# lp.net
KiCad netlist of a schematic drawn in EAGLE
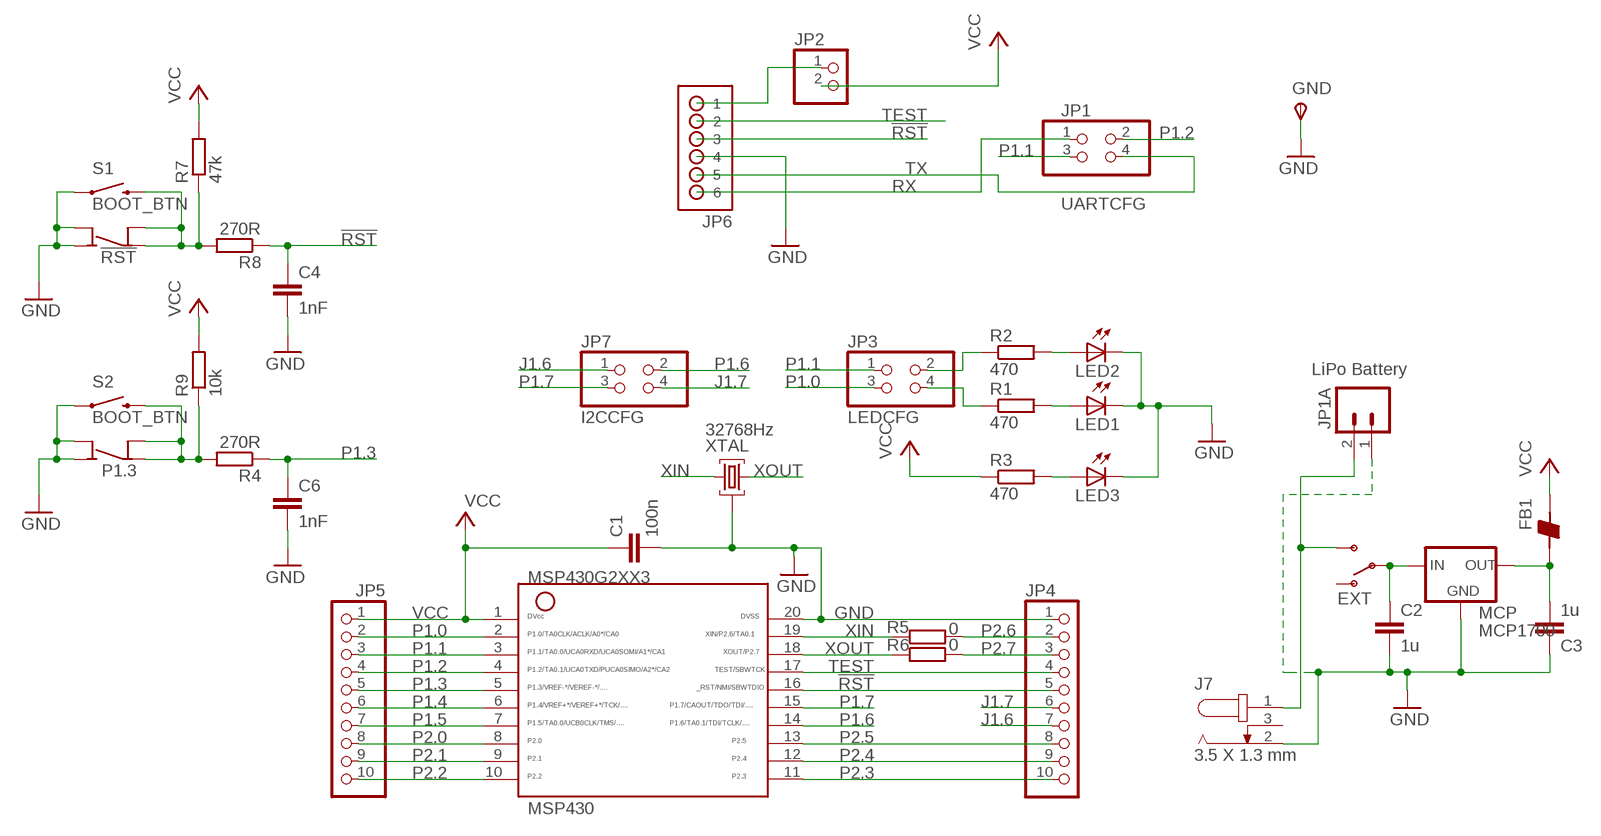
[diagram p0: schematic, sheet 1]

(export (version "E")
  (design (tool "Eeschema 10.0.6"))
  (components
    (comp (ref "!RST")
      (value "!RST")
      (footprint "eagle-import:6MMTACTILE_4PIN")
      (libsource (lib "eagle-import") (part "SPST4"))
    )
    (comp (ref "C1")
      (value "100n")
      (footprint "eagle-import:C0805")
      (libsource (lib "eagle-import") (part "C-EUC0805"))
    )
    (comp (ref "C2")
      (value "1u")
      (footprint "eagle-import:C0805")
      (libsource (lib "eagle-import") (part "C-EUC0805"))
    )
    (comp (ref "C3")
      (value "1u")
      (footprint "eagle-import:C0805")
      (libsource (lib "eagle-import") (part "C-EUC0805"))
    )
    (comp (ref "C4")
      (value "1nF")
      (footprint "eagle-import:C0805")
      (libsource (lib "eagle-import") (part "resistor_C-EUC0805"))
    )
    (comp (ref "C6")
      (value "1nF")
      (footprint "eagle-import:C0805")
      (libsource (lib "eagle-import") (part "resistor_C-EUC0805"))
    )
    (comp (ref "FB1")
      (value "BEAD-0805")
      (footprint "eagle-import:0805")
      (libsource (lib "eagle-import") (part "BEAD-0805"))
    )
    (comp (ref "GND")
      (value "TPSTP20R")
      (footprint "eagle-import:TP20R")
      (libsource (lib "eagle-import") (part "TPSTP20R"))
    )
    (comp (ref "J7")
      (value "3.5 X 1.3 mm")
      (footprint "eagle-import:3.5X1.3MM_DC_JACK")
      (libsource (lib "eagle-import") (part "DC_JACK_3.5X1.3MM"))
    )
    (comp (ref "JP1")
      (value "UARTCFG")
      (footprint "eagle-import:2X02")
      (libsource (lib "eagle-import") (part "PINHD-2X2"))
    )
    (comp (ref "JP1A")
      (value "LiPo Battery")
      (footprint "eagle-import:JST-2-PTH")
      (libsource (lib "eagle-import") (part "M02JST-PTH-2"))
    )
    (comp (ref "JP2")
      (value "PINHD-1X2")
      (footprint "eagle-import:1X02")
      (libsource (lib "eagle-import") (part "PINHD-1X2"))
    )
    (comp (ref "JP3")
      (value "LEDCFG")
      (footprint "eagle-import:2X02")
      (libsource (lib "eagle-import") (part "PINHD-2X2"))
    )
    (comp (ref "JP4")
      (value "PH1X10OCT076")
      (footprint "eagle-import:PH1X10OCT76")
      (libsource (lib "eagle-import") (part "PH1X10OCT076"))
    )
    (comp (ref "JP5")
      (value "PH1X10OCT076")
      (footprint "eagle-import:PH1X10OCT76")
      (libsource (lib "eagle-import") (part "PH1X10OCT076"))
    )
    (comp (ref "JP6")
      (value "No Load")
      (footprint "eagle-import:HDR-1X6_OFFSET")
      (libsource (lib "eagle-import") (part "HDR-1X6-OFFSET"))
    )
    (comp (ref "JP7")
      (value "I2CCFG")
      (footprint "eagle-import:2X02")
      (libsource (lib "eagle-import") (part "PINHD-2X2"))
    )
    (comp (ref "LED1")
      (value "0")
      (footprint "eagle-import:CHIPLED_1206")
      (libsource (lib "eagle-import") (part "LEDCHIPLED_1206"))
    )
    (comp (ref "LED2")
      (value "0")
      (footprint "eagle-import:CHIPLED_1206")
      (libsource (lib "eagle-import") (part "LEDCHIPLED_1206"))
    )
    (comp (ref "LED3")
      (value "0")
      (footprint "eagle-import:CHIPLED_1206")
      (libsource (lib "eagle-import") (part "LEDCHIPLED_1206"))
    )
    (comp (ref "MCP")
      (value "MCP1700")
      (footprint "eagle-import:SOT-23")
      (libsource (lib "eagle-import") (part "MCP1700SOT-23"))
    )
    (comp (ref "MSP430")
      (value "MSP430N")
      (footprint "eagle-import:DIP20_HEX")
      (libsource (lib "eagle-import") (part "G2XX3---N20HEX"))
    )
    (comp (ref "ON")
      (value "EXT")
      (footprint "eagle-import:SWITCH-SPDT")
      (libsource (lib "eagle-import") (part "SWITCH-SPSTPTH"))
    )
    (comp (ref "P1.3")
      (value "P1.3")
      (footprint "eagle-import:6MMTACTILE_4PIN")
      (libsource (lib "eagle-import") (part "SPST4"))
    )
    (comp (ref "R1")
      (value "470")
      (footprint "eagle-import:R0805")
      (libsource (lib "eagle-import") (part "resistor_R-EU_R0805"))
    )
    (comp (ref "R2")
      (value "470")
      (footprint "eagle-import:R0805")
      (libsource (lib "eagle-import") (part "resistor_R-EU_R0805"))
    )
    (comp (ref "R3")
      (value "470")
      (footprint "eagle-import:R0805")
      (libsource (lib "eagle-import") (part "resistor_R-EU_R0805"))
    )
    (comp (ref "R4")
      (value "270R")
      (footprint "eagle-import:R0805")
      (libsource (lib "eagle-import") (part "resistor_R-EU_R0805"))
    )
    (comp (ref "R5")
      (value "0")
      (footprint "eagle-import:R0805")
      (libsource (lib "eagle-import") (part "R-EU_R0805"))
    )
    (comp (ref "R6")
      (value "0")
      (footprint "eagle-import:R0805")
      (libsource (lib "eagle-import") (part "R-EU_R0805"))
    )
    (comp (ref "R7")
      (value "47k")
      (footprint "eagle-import:R0805")
      (libsource (lib "eagle-import") (part "resistor_R-EU_R0805"))
    )
    (comp (ref "R8")
      (value "270R")
      (footprint "eagle-import:R0805")
      (libsource (lib "eagle-import") (part "resistor_R-EU_R0805"))
    )
    (comp (ref "R9")
      (value "10k")
      (footprint "eagle-import:R0805")
      (libsource (lib "eagle-import") (part "resistor_R-EU_R0805"))
    )
    (comp (ref "S1")
      (value "BOOT_BTN")
      (footprint "eagle-import:TACTILE-SWITCH-1101NE")
      (libsource (lib "eagle-import") (part "SWITCH-MOMENTARY-2-SMD-1101NE"))
    )
    (comp (ref "S2")
      (value "BOOT_BTN")
      (footprint "eagle-import:TACTILE-SWITCH-1101NE")
      (libsource (lib "eagle-import") (part "SWITCH-MOMENTARY-2-SMD-1101NE"))
    )
    (comp (ref "XTAL")
      (value "32768Hz")
      (footprint "eagle-import:QUARZ5")
      (libsource (lib "eagle-import") (part "QUARZ5"))
    )
  )
  (nets
    (net (code "1") (name "/J1.6") (class "Default")
      (node (ref "JP4") (pin "7") (pinfunction "7_7") (pintype "passive"))
      (node (ref "JP7") (pin "1") (pinfunction "1_1") (pintype "passive"))
    )
    (net (code "2") (name "/J1.7") (class "Default")
      (node (ref "JP4") (pin "6") (pinfunction "6_6") (pintype "passive"))
      (node (ref "JP7") (pin "4") (pinfunction "4_4") (pintype "passive"))
    )
    (net (code "3") (name "/P1.0") (class "Default")
      (node (ref "JP3") (pin "3") (pinfunction "3_3") (pintype "passive"))
      (node (ref "JP5") (pin "2") (pinfunction "2_2") (pintype "passive"))
      (node (ref "MSP430") (pin "2") (pinfunction "2_2") (pintype "bidirectional"))
    )
    (net (code "4") (name "/P1.1") (class "Default")
      (node (ref "JP1") (pin "3") (pinfunction "3_3") (pintype "passive"))
      (node (ref "JP3") (pin "1") (pinfunction "1_1") (pintype "passive"))
      (node (ref "JP5") (pin "3") (pinfunction "3_3") (pintype "passive"))
      (node (ref "MSP430") (pin "3") (pinfunction "3_3") (pintype "bidirectional"))
    )
    (net (code "5") (name "/P1.2") (class "Default")
      (node (ref "JP1") (pin "2") (pinfunction "2_2") (pintype "passive"))
      (node (ref "JP5") (pin "4") (pinfunction "4_4") (pintype "passive"))
      (node (ref "MSP430") (pin "4") (pinfunction "4_4") (pintype "bidirectional"))
    )
    (net (code "6") (name "/P1.3") (class "Default")
      (node (ref "C6") (pin "1") (pinfunction "1_1") (pintype "passive"))
      (node (ref "JP5") (pin "5") (pinfunction "5_5") (pintype "passive"))
      (node (ref "MSP430") (pin "5") (pinfunction "5_5") (pintype "bidirectional"))
      (node (ref "R4") (pin "1") (pinfunction "1_1") (pintype "passive"))
    )
    (net (code "7") (name "/P1.4") (class "Default")
      (node (ref "JP5") (pin "6") (pinfunction "6_6") (pintype "passive"))
      (node (ref "MSP430") (pin "6") (pinfunction "6_6") (pintype "bidirectional"))
    )
    (net (code "8") (name "/P1.5") (class "Default")
      (node (ref "JP5") (pin "7") (pinfunction "7_7") (pintype "passive"))
      (node (ref "MSP430") (pin "7") (pinfunction "7_7") (pintype "bidirectional"))
    )
    (net (code "9") (name "/P1.6") (class "Default")
      (node (ref "JP7") (pin "2") (pinfunction "2_2") (pintype "passive"))
      (node (ref "MSP430") (pin "14") (pinfunction "14_14") (pintype "bidirectional"))
    )
    (net (code "10") (name "/P1.7") (class "Default")
      (node (ref "JP7") (pin "3") (pinfunction "3_3") (pintype "passive"))
      (node (ref "MSP430") (pin "15") (pinfunction "15_15") (pintype "bidirectional"))
    )
    (net (code "11") (name "/P2.0") (class "Default")
      (node (ref "JP5") (pin "8") (pinfunction "8_8") (pintype "passive"))
      (node (ref "MSP430") (pin "8") (pinfunction "8_8") (pintype "bidirectional"))
    )
    (net (code "12") (name "/P2.1") (class "Default")
      (node (ref "JP5") (pin "9") (pinfunction "9_9") (pintype "passive"))
      (node (ref "MSP430") (pin "9") (pinfunction "9_9") (pintype "bidirectional"))
    )
    (net (code "13") (name "/P2.2") (class "Default")
      (node (ref "JP5") (pin "10") (pinfunction "10_10") (pintype "passive"))
      (node (ref "MSP430") (pin "10") (pinfunction "10_10") (pintype "bidirectional"))
    )
    (net (code "14") (name "/P2.3") (class "Default")
      (node (ref "JP4") (pin "10") (pinfunction "10_10") (pintype "passive"))
      (node (ref "MSP430") (pin "11") (pinfunction "11_11") (pintype "bidirectional"))
    )
    (net (code "15") (name "/P2.4") (class "Default")
      (node (ref "JP4") (pin "9") (pinfunction "9_9") (pintype "passive"))
      (node (ref "MSP430") (pin "12") (pinfunction "12_12") (pintype "bidirectional"))
    )
    (net (code "16") (name "/P2.5") (class "Default")
      (node (ref "JP4") (pin "8") (pinfunction "8_8") (pintype "passive"))
      (node (ref "MSP430") (pin "13") (pinfunction "13_13") (pintype "bidirectional"))
    )
    (net (code "17") (name "/P2.6") (class "Default")
      (node (ref "JP4") (pin "2") (pinfunction "2_2") (pintype "passive"))
      (node (ref "R5") (pin "2") (pinfunction "2_2") (pintype "passive"))
    )
    (net (code "18") (name "/P2.7") (class "Default")
      (node (ref "JP4") (pin "3") (pinfunction "3_3") (pintype "passive"))
      (node (ref "R6") (pin "2") (pinfunction "2_2") (pintype "passive"))
    )
    (net (code "19") (name "/RX") (class "Default")
      (node (ref "JP1") (pin "1") (pinfunction "1_1") (pintype "passive"))
      (node (ref "JP6") (pin "6") (pinfunction "6_6") (pintype "passive"))
    )
    (net (code "20") (name "/TEST") (class "Default")
      (node (ref "JP4") (pin "4") (pinfunction "4_4") (pintype "passive"))
      (node (ref "JP6") (pin "2") (pinfunction "2_2") (pintype "passive"))
      (node (ref "MSP430") (pin "17") (pinfunction "17_17") (pintype "bidirectional"))
    )
    (net (code "21") (name "/TX") (class "Default")
      (node (ref "JP1") (pin "4") (pinfunction "4_4") (pintype "passive"))
      (node (ref "JP6") (pin "5") (pinfunction "5_5") (pintype "passive"))
    )
    (net (code "22") (name "/XIN") (class "Default")
      (node (ref "MSP430") (pin "19") (pinfunction "19_19") (pintype "bidirectional"))
      (node (ref "R5") (pin "1") (pinfunction "1_1") (pintype "passive"))
      (node (ref "XTAL") (pin "2") (pinfunction "2_2") (pintype "passive"))
    )
    (net (code "23") (name "/XOUT") (class "Default")
      (node (ref "MSP430") (pin "18") (pinfunction "18_18") (pintype "bidirectional"))
      (node (ref "R6") (pin "1") (pinfunction "1_1") (pintype "passive"))
      (node (ref "XTAL") (pin "1") (pinfunction "1_1") (pintype "passive"))
    )
    (net (code "24") (name "/~{RST}") (class "Default")
      (node (ref "C4") (pin "1") (pinfunction "1_1") (pintype "passive"))
      (node (ref "JP4") (pin "5") (pinfunction "5_5") (pintype "passive"))
      (node (ref "JP6") (pin "3") (pinfunction "3_3") (pintype "passive"))
      (node (ref "MSP430") (pin "16") (pinfunction "16_16") (pintype "bidirectional"))
      (node (ref "R8") (pin "1") (pinfunction "1_1") (pintype "passive"))
    )
    (net (code "25") (name "GND") (class "Default")
      (node (ref "!RST") (pin "A1") (pinfunction "NO_A1") (pintype "passive"))
      (node (ref "!RST") (pin "A2") (pinfunction "NO_A2") (pintype "passive"))
      (node (ref "C1") (pin "2") (pinfunction "2_2") (pintype "passive"))
      (node (ref "C2") (pin "2") (pinfunction "2_2") (pintype "passive"))
      (node (ref "C3") (pin "1") (pinfunction "1_1") (pintype "passive"))
      (node (ref "C4") (pin "2") (pinfunction "2_2") (pintype "passive"))
      (node (ref "C6") (pin "2") (pinfunction "2_2") (pintype "passive"))
      (node (ref "GND") (pin "TP") (pinfunction "PP_TP") (pintype "input"))
      (node (ref "J7") (pin "2") (pinfunction "2_2") (pintype "passive"))
      (node (ref "JP1A") (pin "1") (pinfunction "1_1") (pintype "passive"))
      (node (ref "JP4") (pin "1") (pinfunction "1_1") (pintype "passive"))
      (node (ref "JP6") (pin "4") (pinfunction "4_4") (pintype "passive"))
      (node (ref "LED1") (pin "C") (pinfunction "C_C") (pintype "passive"))
      (node (ref "LED2") (pin "C") (pinfunction "C_C") (pintype "passive"))
      (node (ref "LED3") (pin "C") (pinfunction "C_C") (pintype "passive"))
      (node (ref "MCP") (pin "1") (pinfunction "GND_1") (pintype "input"))
      (node (ref "MSP430") (pin "20") (pinfunction "20_20") (pintype "bidirectional"))
      (node (ref "P1.3") (pin "A1") (pinfunction "NO_A1") (pintype "passive"))
      (node (ref "P1.3") (pin "A2") (pinfunction "NO_A2") (pintype "passive"))
      (node (ref "S1") (pin "1") (pinfunction "1_1") (pintype "passive"))
      (node (ref "S2") (pin "1") (pinfunction "1_1") (pintype "passive"))
      (node (ref "XTAL") (pin "GND@0") (pinfunction "0_GND@0") (pintype "passive"))
    )
    (net (code "26") (name "Net-(!RST-COM-PadB1)") (class "Default")
      (node (ref "!RST") (pin "B1") (pinfunction "COM_B1") (pintype "passive"))
      (node (ref "!RST") (pin "B2") (pinfunction "COM_B2") (pintype "passive"))
      (node (ref "R7") (pin "1") (pinfunction "1_1") (pintype "passive"))
      (node (ref "R8") (pin "2") (pinfunction "2_2") (pintype "passive"))
      (node (ref "S1") (pin "2") (pinfunction "2_2") (pintype "passive"))
    )
    (net (code "27") (name "Net-(FB1-P$1)") (class "Default")
      (node (ref "C3") (pin "2") (pinfunction "2_2") (pintype "passive"))
      (node (ref "FB1") (pin "1") (pinfunction "P$1_1") (pintype "passive"))
      (node (ref "MCP") (pin "2") (pinfunction "OUT_2") (pintype "passive"))
    )
    (net (code "28") (name "Net-(JP2-Pad1)") (class "Default")
      (node (ref "JP2") (pin "1") (pinfunction "1_1") (pintype "passive"))
      (node (ref "JP6") (pin "1") (pinfunction "1_1") (pintype "passive"))
    )
    (net (code "29") (name "Net-(JP3-Pad2)") (class "Default")
      (node (ref "JP3") (pin "2") (pinfunction "2_2") (pintype "passive"))
      (node (ref "R2") (pin "1") (pinfunction "1_1") (pintype "passive"))
    )
    (net (code "30") (name "Net-(JP3-Pad4)") (class "Default")
      (node (ref "JP3") (pin "4") (pinfunction "4_4") (pintype "passive"))
      (node (ref "R1") (pin "1") (pinfunction "1_1") (pintype "passive"))
    )
    (net (code "31") (name "Net-(LED1-PadA)") (class "Default")
      (node (ref "LED1") (pin "A") (pinfunction "A_A") (pintype "passive"))
      (node (ref "R1") (pin "2") (pinfunction "2_2") (pintype "passive"))
    )
    (net (code "32") (name "Net-(LED2-PadA)") (class "Default")
      (node (ref "LED2") (pin "A") (pinfunction "A_A") (pintype "passive"))
      (node (ref "R2") (pin "2") (pinfunction "2_2") (pintype "passive"))
    )
    (net (code "33") (name "Net-(LED3-PadA)") (class "Default")
      (node (ref "LED3") (pin "A") (pinfunction "A_A") (pintype "passive"))
      (node (ref "R3") (pin "2") (pinfunction "2_2") (pintype "passive"))
    )
    (net (code "34") (name "Net-(MCP-IN)") (class "Default")
      (node (ref "C2") (pin "1") (pinfunction "1_1") (pintype "passive"))
      (node (ref "MCP") (pin "3") (pinfunction "IN_3") (pintype "input"))
      (node (ref "ON") (pin "2") (pinfunction "P_2") (pintype "passive"))
    )
    (net (code "35") (name "Net-(ON-S)") (class "Default")
      (node (ref "J7") (pin "1") (pinfunction "1_1") (pintype "passive"))
      (node (ref "JP1A") (pin "2") (pinfunction "2_2") (pintype "passive"))
      (node (ref "ON") (pin "3") (pinfunction "S_3") (pintype "passive"))
    )
    (net (code "36") (name "Net-(P1.3-COM-PadB1)") (class "Default")
      (node (ref "P1.3") (pin "B1") (pinfunction "COM_B1") (pintype "passive"))
      (node (ref "P1.3") (pin "B2") (pinfunction "COM_B2") (pintype "passive"))
      (node (ref "R4") (pin "2") (pinfunction "2_2") (pintype "passive"))
      (node (ref "R9") (pin "1") (pinfunction "1_1") (pintype "passive"))
      (node (ref "S2") (pin "2") (pinfunction "2_2") (pintype "passive"))
    )
    (net (code "37") (name "VCC") (class "Default")
      (node (ref "C1") (pin "1") (pinfunction "1_1") (pintype "passive"))
      (node (ref "FB1") (pin "2") (pinfunction "P$2_2") (pintype "passive"))
      (node (ref "JP2") (pin "2") (pinfunction "2_2") (pintype "passive"))
      (node (ref "JP5") (pin "1") (pinfunction "1_1") (pintype "passive"))
      (node (ref "MSP430") (pin "1") (pinfunction "1_1") (pintype "bidirectional"))
      (node (ref "R3") (pin "1") (pinfunction "1_1") (pintype "passive"))
      (node (ref "R7") (pin "2") (pinfunction "2_2") (pintype "passive"))
      (node (ref "R9") (pin "2") (pinfunction "2_2") (pintype "passive"))
    )
    (net (code "38") (name "unconnected-(J7-Pad3)") (class "Default")
      (node (ref "J7") (pin "3") (pinfunction "3_3") (pintype "passive"))
    )
    (net (code "39") (name "unconnected-(ON-O-Pad1)") (class "Default")
      (node (ref "ON") (pin "1") (pinfunction "O_1") (pintype "passive"))
    )
  )
)
